# Sensor_Board.net
KiCad netlist of a schematic drawn in Altium Designer
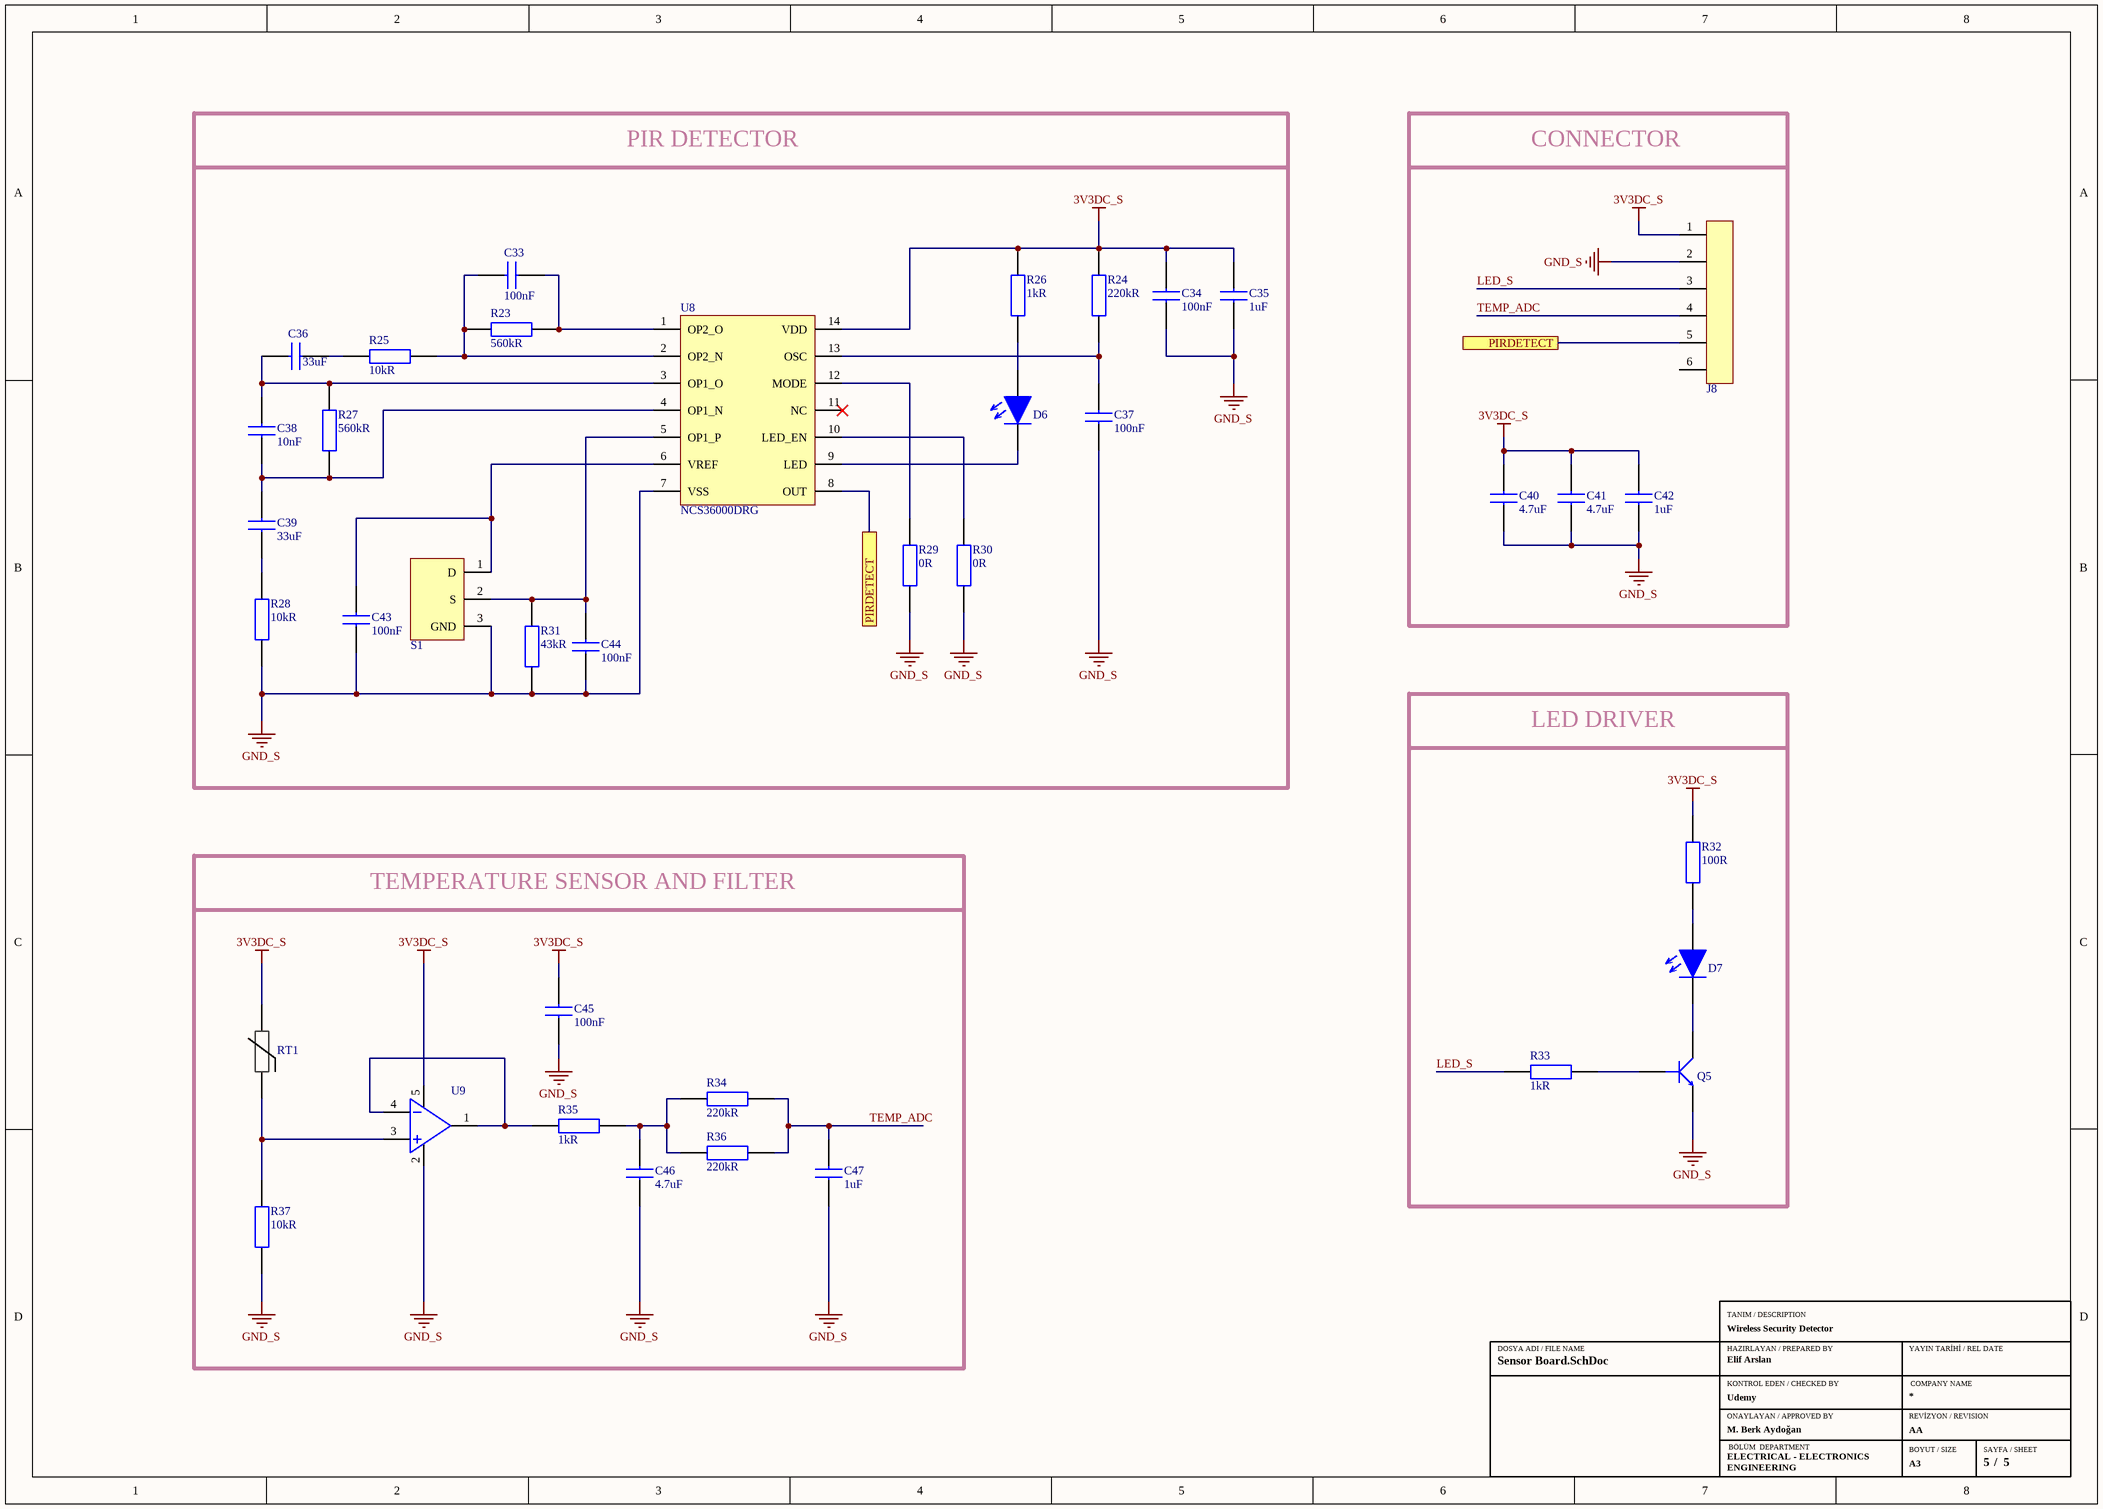
[diagram p0: Sensor Board.SchDoc]

(export (version "E")
  (design (tool "Eeschema 10.0.6"))
  (components
    (comp (ref "C33")
      (value "C0603C104K4RACTU")
      (footprint "CAP_0603")
      (description "CAP CER 100nF %10 0603 SMD")
      (fields
        (field (name "MANUFACTURER") "KEMET")
        (field (name "TOLERANCE") "10%")
        (field (name "CAPACITANCE") "100nF")
      )
      (libsource (lib "UDEMY_Library") (part "CAP CER 100nF 0603"))
    )
    (comp (ref "C34")
      (value "C0603C104K4RACTU")
      (footprint "CAP_0603")
      (description "CAP CER 100nF %10 0603 SMD")
      (fields
        (field (name "MANUFACTURER") "KEMET")
        (field (name "TOLERANCE") "10%")
        (field (name "CAPACITANCE") "100nF")
      )
      (libsource (lib "UDEMY_Library") (part "CAP CER 100nF 0603"))
    )
    (comp (ref "C35")
      (value "CL21B105KBFNNNE")
      (footprint "CAP_0805")
      (description "CAP CER 1UF %10 50V 0805")
      (fields
        (field (name "MANUFACTURER") "Samsung")
        (field (name "TOLERANCE") "10%")
        (field (name "CAPACITANCE") "1uF")
      )
      (libsource (lib "UDEMY_Library") (part "CAP CER 1uF 0805"))
    )
    (comp (ref "C36")
      (value "C3216X5R1E336M160AC")
      (footprint "RES_1206")
      (description "CAP CER 33uF %20 1206")
      (fields
        (field (name "MANUFACTURER") "TDK")
        (field (name "TOLERANCE") "20%")
        (field (name "CAPACITANCE") "33uF")
      )
      (libsource (lib "UDEMY_Library") (part "CAP CER 33uF 1206"))
    )
    (comp (ref "C37")
      (value "C0603C104K4RACTU")
      (footprint "CAP_0603")
      (description "CAP CER 100nF %10 0603 SMD")
      (fields
        (field (name "MANUFACTURER") "KEMET")
        (field (name "TOLERANCE") "10%")
        (field (name "CAPACITANCE") "100nF")
      )
      (libsource (lib "UDEMY_Library") (part "CAP CER 100nF 0603"))
    )
    (comp (ref "C38")
      (value "0603B103K160CT")
      (footprint "CAP_0603")
      (description "CAP CER 10nF %10 0603")
      (fields
        (field (name "MANUFACTURER") "Walsin Technologies")
        (field (name "TOLERANCE") "10%")
        (field (name "CAPACITANCE") "10nF")
      )
      (libsource (lib "UDEMY_Library") (part "CAP CER 10nF 0603"))
    )
    (comp (ref "C39")
      (value "C3216X5R1E336M160AC")
      (footprint "RES_1206")
      (description "CAP CER 33uF %20 1206")
      (fields
        (field (name "MANUFACTURER") "TDK")
        (field (name "TOLERANCE") "20%")
        (field (name "CAPACITANCE") "33uF")
      )
      (libsource (lib "UDEMY_Library") (part "CAP CER 33uF 1206"))
    )
    (comp (ref "C40")
      (value "CL21A475KAQNNNE")
      (footprint "CAP_0805")
      (description "CAP CER 4.7UF 25V X5R %10 0805")
      (fields
        (field (name "MANUFACTURER") "Samsung")
        (field (name "TOLERANCE") "10%")
        (field (name "CAPACITANCE") "4.7uF")
      )
      (libsource (lib "UDEMY_Library") (part "CAP CER  4.7uF 0805"))
    )
    (comp (ref "C41")
      (value "CL21A475KAQNNNE")
      (footprint "CAP_0805")
      (description "CAP CER 4.7UF 25V X5R %10 0805")
      (fields
        (field (name "MANUFACTURER") "Samsung")
        (field (name "TOLERANCE") "10%")
        (field (name "CAPACITANCE") "4.7uF")
      )
      (libsource (lib "UDEMY_Library") (part "CAP CER  4.7uF 0805"))
    )
    (comp (ref "C42")
      (value "CL21B105KBFNNNE")
      (footprint "CAP_0805")
      (description "CAP CER 1UF %10 50V 0805")
      (fields
        (field (name "MANUFACTURER") "Samsung")
        (field (name "TOLERANCE") "10%")
        (field (name "CAPACITANCE") "1uF")
      )
      (libsource (lib "UDEMY_Library") (part "CAP CER 1uF 0805"))
    )
    (comp (ref "C43")
      (value "C0603C104K4RACTU")
      (footprint "CAP_0603")
      (description "CAP CER 100nF %10 0603 SMD")
      (fields
        (field (name "MANUFACTURER") "KEMET")
        (field (name "TOLERANCE") "10%")
        (field (name "CAPACITANCE") "100nF")
      )
      (libsource (lib "UDEMY_Library") (part "CAP CER 100nF 0603"))
    )
    (comp (ref "C44")
      (value "C0603C104K4RACTU")
      (footprint "CAP_0603")
      (description "CAP CER 100nF %10 0603 SMD")
      (fields
        (field (name "MANUFACTURER") "KEMET")
        (field (name "TOLERANCE") "10%")
        (field (name "CAPACITANCE") "100nF")
      )
      (libsource (lib "UDEMY_Library") (part "CAP CER 100nF 0603"))
    )
    (comp (ref "C45")
      (value "C0603C104K4RACTU")
      (footprint "CAP_0603")
      (description "CAP CER 100nF %10 0603 SMD")
      (fields
        (field (name "MANUFACTURER") "KEMET")
        (field (name "TOLERANCE") "10%")
        (field (name "CAPACITANCE") "100nF")
      )
      (libsource (lib "UDEMY_Library") (part "CAP CER 100nF 0603"))
    )
    (comp (ref "C46")
      (value "CL21A475KAQNNNE")
      (footprint "CAP_0805")
      (description "CAP CER 4.7UF 25V X5R %10 0805")
      (fields
        (field (name "MANUFACTURER") "Samsung")
        (field (name "TOLERANCE") "10%")
        (field (name "CAPACITANCE") "4.7uF")
      )
      (libsource (lib "UDEMY_Library") (part "CAP CER  4.7uF 0805"))
    )
    (comp (ref "C47")
      (value "CL21B105KBFNNNE")
      (footprint "CAP_0805")
      (description "CAP CER 1UF %10 50V 0805")
      (fields
        (field (name "MANUFACTURER") "Samsung")
        (field (name "TOLERANCE") "10%")
        (field (name "CAPACITANCE") "1uF")
      )
      (libsource (lib "UDEMY_Library") (part "CAP CER 1uF 0805"))
    )
    (comp (ref "D6")
      (value "LTST-C171GKT")
      (footprint "LED_GREEN_0805")
      (description "Green 569nm LED Indication - Discrete 2.1V 0805 (2012 Metric)")
      (fields (field (name "MANUFACTURER") "Vishay Lite-On"))
      (libsource (lib "UDEMY_Library") (part "LED GREEN 0805"))
    )
    (comp (ref "D7")
      (value "LH R974-LP-1-0-20-R18")
      (footprint "LED_RED_0805")
      (description "LED Uni-Color Hyper Red 660nm 2-Pin Chip 0805(2012Metric) T/R")
      (fields
        (field (name "MANUFACTURER") "Osram Opto")
        (field (name "MANUFACTURER PART NUMBER") "LH R974-LP-1")
      )
      (libsource (lib "UDEMY_Library") (part "LED RED 0805"))
    )
    (comp (ref "J8")
      (value "64800611622")
      (footprint "64800611622")
      (description "1.5mm 6PIN Connector")
      (fields (field (name "MANUFACTURER") "Wurth Electronics"))
      (libsource (lib "UDEMY_Library") (part "64800611622_conn_6pin"))
    )
    (comp (ref "Q5")
      (value "MMBT3904-7-F")
      (footprint "SOT-23F")
      (description "Bipolar (BJT) Transistor NPN 40 V 200 mA 300MHz 300 mW Surface Mount SOT-23-3")
      (fields (field (name "MANUFACTURER") "Diodes Zetex"))
      (libsource (lib "UDEMY_Library") (part "MMBT3904-7-F"))
    )
    (comp (ref "R23")
      (value "RC0603JR-07560KL")
      (footprint "RES_0603")
      (description "RES SMD 560K OHM 5% 1/10W 0603")
      (fields
        (field (name "MANUFACTURER") "Yageo")
        (field (name "TOLERANCE") "5%")
        (field (name "RESISTANCE") "560kR")
      )
      (libsource (lib "UDEMY_Library") (part "RES 560K OHM 0603"))
    )
    (comp (ref "R24")
      (value "RC0603JR-07220KL")
      (footprint "RES_0603")
      (description "RES 220K OHM %5 0603 SMD")
      (fields
        (field (name "MANUFACTURER") "Yageo")
        (field (name "TOLERANCE") "5%")
        (field (name "RESISTANCE") "220kR")
      )
      (libsource (lib "UDEMY_Library") (part "RES 220K OHM 0603"))
    )
    (comp (ref "R25")
      (value "RC0603FR-0710KL")
      (footprint "RES_0603")
      (description "RES 10K %1 OHM 0603 SMD")
      (fields
        (field (name "MANUFACTURER") "Yageo")
        (field (name "TOLERANCE") "1%")
        (field (name "RESISTANCE") "10kR")
      )
      (libsource (lib "UDEMY_Library") (part "RES 10K OHM 0603"))
    )
    (comp (ref "R26")
      (value "RC0603FR-071KL")
      (footprint "RES_0603")
      (description "RES SMD 1K OHM %1 0603")
      (fields
        (field (name "MANUFACTURER") "Yageo")
        (field (name "TOLERANCE") "1%")
        (field (name "RESISTANCE") "1kR")
      )
      (libsource (lib "UDEMY_Library") (part "RES 1K OHM 0603"))
    )
    (comp (ref "R27")
      (value "RC0603JR-07560KL")
      (footprint "RES_0603")
      (description "RES SMD 560K OHM 5% 1/10W 0603")
      (fields
        (field (name "MANUFACTURER") "Yageo")
        (field (name "TOLERANCE") "5%")
        (field (name "RESISTANCE") "560kR")
      )
      (libsource (lib "UDEMY_Library") (part "RES 560K OHM 0603"))
    )
    (comp (ref "R28")
      (value "RC0603FR-0710KL")
      (footprint "RES_0603")
      (description "RES 10K %1 OHM 0603 SMD")
      (fields
        (field (name "MANUFACTURER") "Yageo")
        (field (name "TOLERANCE") "1%")
        (field (name "RESISTANCE") "10kR")
      )
      (libsource (lib "UDEMY_Library") (part "RES 10K OHM 0603"))
    )
    (comp (ref "R29")
      (value "RC0603JR-070RL")
      (footprint "RES_0603")
      (description "RES SMD 0 OHM JUMPER 1/10W 0603")
      (fields
        (field (name "MANUFACTURER") "Yageo")
        (field (name "TOLERANCE") "1%")
        (field (name "RESISTANCE") "0R")
      )
      (libsource (lib "UDEMY_Library") (part "RES 0 OHM 0603"))
    )
    (comp (ref "R30")
      (value "RC0603JR-070RL")
      (footprint "RES_0603")
      (description "RES SMD 0 OHM JUMPER 1/10W 0603")
      (fields
        (field (name "MANUFACTURER") "Yageo")
        (field (name "TOLERANCE") "1%")
        (field (name "RESISTANCE") "0R")
      )
      (libsource (lib "UDEMY_Library") (part "RES 0 OHM 0603"))
    )
    (comp (ref "R31")
      (value "RC0603JR-0743KL")
      (footprint "RES_0603")
      (description "RES 43K OHM %5 0603 SMD")
      (fields
        (field (name "MANUFACTURER") "Yageo")
        (field (name "TOLERANCE") "5%")
        (field (name "RESISTANCE") "43kR")
      )
      (libsource (lib "UDEMY_Library") (part "RES 43K OHM 0603"))
    )
    (comp (ref "R32")
      (value "RC0603JR-07100RL")
      (footprint "RES_0603")
      (description "RES 100 %5 OHM 0603 SMD")
      (fields
        (field (name "MANUFACTURER") "Yageo")
        (field (name "TOLERANCE") "5%")
        (field (name "RESISTANCE") "100R")
      )
      (libsource (lib "UDEMY_Library") (part "RES 100 OHM 0603"))
    )
    (comp (ref "R33")
      (value "RC0603FR-071KL")
      (footprint "RES_0603")
      (description "RES SMD 1K OHM %1 0603")
      (fields
        (field (name "MANUFACTURER") "Yageo")
        (field (name "TOLERANCE") "1%")
        (field (name "RESISTANCE") "1kR")
      )
      (libsource (lib "UDEMY_Library") (part "RES 1K OHM 0603"))
    )
    (comp (ref "R34")
      (value "RC0603JR-07220KL")
      (footprint "RES_0603")
      (description "RES 220K OHM %5 0603 SMD")
      (fields
        (field (name "MANUFACTURER") "Yageo")
        (field (name "TOLERANCE") "5%")
        (field (name "RESISTANCE") "220kR")
      )
      (libsource (lib "UDEMY_Library") (part "RES 220K OHM 0603"))
    )
    (comp (ref "R35")
      (value "RC0603FR-071KL")
      (footprint "RES_0603")
      (description "RES SMD 1K OHM %1 0603")
      (fields
        (field (name "MANUFACTURER") "Yageo")
        (field (name "TOLERANCE") "1%")
        (field (name "RESISTANCE") "1kR")
      )
      (libsource (lib "UDEMY_Library") (part "RES 1K OHM 0603"))
    )
    (comp (ref "R36")
      (value "RC0603JR-07220KL")
      (footprint "RES_0603")
      (description "RES 220K OHM %5 0603 SMD")
      (fields
        (field (name "MANUFACTURER") "Yageo")
        (field (name "TOLERANCE") "5%")
        (field (name "RESISTANCE") "220kR")
      )
      (libsource (lib "UDEMY_Library") (part "RES 220K OHM 0603"))
    )
    (comp (ref "R37")
      (value "RC0603FR-0710KL")
      (footprint "RES_0603")
      (description "RES 10K %1 OHM 0603 SMD")
      (fields
        (field (name "MANUFACTURER") "Yageo")
        (field (name "TOLERANCE") "1%")
        (field (name "RESISTANCE") "10kR")
      )
      (libsource (lib "UDEMY_Library") (part "RES 10K OHM 0603"))
    )
    (comp (ref "RT1")
      (value "TFPT1206L1002FM")
      (footprint "RES_1206")
      (description "Thermistor PTC 10K Ohm 1% 2-Pin 1206 Surface Mount Solder Pad T/R Automotive")
      (fields (field (name "MANUFACTURER") "Vishay Dale") (field (name "TOLERANCE") "1%"))
      (libsource (lib "UDEMY_Library") (part "TFPT1206L1002FM"))
    )
    (comp (ref "S1")
      (value "LHI 878/3902")
      (footprint "LHI 878")
      (description "Sensor Pyro Detector Dual Motion")
      (fields (field (name "MANUFACTURER") "Excelitas Technology"))
      (libsource (lib "UDEMY_Library") (part "LHI 878/3902"))
    )
    (comp (ref "U8")
      (value "NCS36000DRG")
      (footprint "SOIC14")
      (description "PIR Controller Low Noise Amplifiers and LDO Regulator 14-Pin SOIC N T/R")
      (fields (field (name "MANUFACTURER") "ON Semiconductor"))
      (libsource (lib "UDEMY_Library") (part "NCS 36000"))
    )
    (comp (ref "U9")
      (value "OPA314AIDBVR")
      (footprint "SOT23-5")
      (description "Op Amp OPA314 \r\nSOT23-5")
      (fields (field (name "MANUFACTURER") "Texas Instruments"))
      (libsource (lib "UDEMY_Library") (part "OPA314"))
    )
  )
  (nets
    (net (code "1") (name "/LED_S") (class "Default")
      (node (ref "J8") (pin "3") (pinfunction "3_3") (pintype "passive"))
      (node (ref "R33") (pin "1") (pinfunction "1_1") (pintype "passive"))
    )
    (net (code "2") (name "/PIRDETECT") (class "Default")
      (node (ref "J8") (pin "5") (pinfunction "5_5") (pintype "passive"))
      (node (ref "U8") (pin "8") (pinfunction "OUT_8") (pintype "passive"))
    )
    (net (code "3") (name "/TEMP_ADC") (class "Default")
      (node (ref "C47") (pin "2") (pinfunction "2_2") (pintype "passive"))
      (node (ref "J8") (pin "4") (pinfunction "4_4") (pintype "passive"))
      (node (ref "R34") (pin "2") (pinfunction "2_2") (pintype "passive"))
      (node (ref "R36") (pin "2") (pinfunction "2_2") (pintype "passive"))
    )
    (net (code "4") (name "3V3DC_S") (class "Default")
      (node (ref "C34") (pin "2") (pinfunction "2_2") (pintype "passive"))
      (node (ref "C35") (pin "2") (pinfunction "2_2") (pintype "passive"))
      (node (ref "C40") (pin "2") (pinfunction "2_2") (pintype "passive"))
      (node (ref "C41") (pin "2") (pinfunction "2_2") (pintype "passive"))
      (node (ref "C42") (pin "2") (pinfunction "2_2") (pintype "passive"))
      (node (ref "C45") (pin "2") (pinfunction "2_2") (pintype "passive"))
      (node (ref "J8") (pin "1") (pinfunction "1_1") (pintype "passive"))
      (node (ref "R24") (pin "2") (pinfunction "2_2") (pintype "passive"))
      (node (ref "R26") (pin "2") (pinfunction "2_2") (pintype "passive"))
      (node (ref "R32") (pin "2") (pinfunction "2_2") (pintype "passive"))
      (node (ref "RT1") (pin "2") (pinfunction "2_2") (pintype "passive"))
      (node (ref "U8") (pin "14") (pinfunction "VDD_14") (pintype "passive"))
      (node (ref "U9") (pin "5") (pinfunction "5_5") (pintype "passive"))
    )
    (net (code "5") (name "GND_S") (class "Default")
      (node (ref "C34") (pin "1") (pinfunction "1_1") (pintype "passive"))
      (node (ref "C35") (pin "1") (pinfunction "1_1") (pintype "passive"))
      (node (ref "C37") (pin "1") (pinfunction "1_1") (pintype "passive"))
      (node (ref "C40") (pin "1") (pinfunction "1_1") (pintype "passive"))
      (node (ref "C41") (pin "1") (pinfunction "1_1") (pintype "passive"))
      (node (ref "C42") (pin "1") (pinfunction "1_1") (pintype "passive"))
      (node (ref "C43") (pin "1") (pinfunction "1_1") (pintype "passive"))
      (node (ref "C44") (pin "1") (pinfunction "1_1") (pintype "passive"))
      (node (ref "C45") (pin "1") (pinfunction "1_1") (pintype "passive"))
      (node (ref "C46") (pin "1") (pinfunction "1_1") (pintype "passive"))
      (node (ref "C47") (pin "1") (pinfunction "1_1") (pintype "passive"))
      (node (ref "J8") (pin "2") (pinfunction "2_2") (pintype "passive"))
      (node (ref "Q5") (pin "2") (pinfunction "E_2") (pintype "passive"))
      (node (ref "R28") (pin "1") (pinfunction "1_1") (pintype "passive"))
      (node (ref "R29") (pin "1") (pinfunction "1_1") (pintype "passive"))
      (node (ref "R30") (pin "1") (pinfunction "1_1") (pintype "passive"))
      (node (ref "R31") (pin "1") (pinfunction "1_1") (pintype "passive"))
      (node (ref "R37") (pin "1") (pinfunction "1_1") (pintype "passive"))
      (node (ref "S1") (pin "3") (pinfunction "GND_3") (pintype "passive"))
      (node (ref "U8") (pin "7") (pinfunction "VSS_7") (pintype "passive"))
      (node (ref "U9") (pin "2") (pinfunction "2_2") (pintype "passive"))
    )
    (net (code "6") (name "Net-(C36-Pad2)") (class "Default")
      (node (ref "C36") (pin "2") (pinfunction "2_2") (pintype "passive"))
      (node (ref "R25") (pin "1") (pinfunction "1_1") (pintype "passive"))
    )
    (net (code "7") (name "Net-(C39-Pad1)") (class "Default")
      (node (ref "C39") (pin "1") (pinfunction "1_1") (pintype "passive"))
      (node (ref "R28") (pin "2") (pinfunction "2_2") (pintype "passive"))
    )
    (net (code "8") (name "Net-(C46-Pad2)") (class "Default")
      (node (ref "C46") (pin "2") (pinfunction "2_2") (pintype "passive"))
      (node (ref "R34") (pin "1") (pinfunction "1_1") (pintype "passive"))
      (node (ref "R35") (pin "2") (pinfunction "2_2") (pintype "passive"))
      (node (ref "R36") (pin "1") (pinfunction "1_1") (pintype "passive"))
    )
    (net (code "9") (name "Net-(D6-Pad2)") (class "Default")
      (node (ref "D6") (pin "2") (pinfunction "2_2") (pintype "passive"))
      (node (ref "R26") (pin "1") (pinfunction "1_1") (pintype "passive"))
    )
    (net (code "10") (name "Net-(D7-Pad2)") (class "Default")
      (node (ref "D7") (pin "2") (pinfunction "2_2") (pintype "passive"))
      (node (ref "R32") (pin "1") (pinfunction "1_1") (pintype "passive"))
    )
    (net (code "11") (name "Net-(Q5-B)") (class "Default")
      (node (ref "Q5") (pin "1") (pinfunction "B_1") (pintype "passive"))
      (node (ref "R33") (pin "2") (pinfunction "2_2") (pintype "passive"))
    )
    (net (code "12") (name "Net-(Q5-C)") (class "Default")
      (node (ref "D7") (pin "1") (pinfunction "1_1") (pintype "passive"))
      (node (ref "Q5") (pin "3") (pinfunction "C_3") (pintype "passive"))
    )
    (net (code "13") (name "Net-(R35-Pad1)") (class "Default")
      (node (ref "R35") (pin "1") (pinfunction "1_1") (pintype "passive"))
      (node (ref "U9") (pin "1") (pinfunction "1_1") (pintype "passive"))
      (node (ref "U9") (pin "4") (pinfunction "4_4") (pintype "passive"))
    )
    (net (code "14") (name "Net-(R37-Pad2)") (class "Default")
      (node (ref "R37") (pin "2") (pinfunction "2_2") (pintype "passive"))
      (node (ref "RT1") (pin "1") (pinfunction "1_1") (pintype "passive"))
      (node (ref "U9") (pin "3") (pinfunction "3_3") (pintype "passive"))
    )
    (net (code "15") (name "Net-(S1-D)") (class "Default")
      (node (ref "C43") (pin "2") (pinfunction "2_2") (pintype "passive"))
      (node (ref "S1") (pin "1") (pinfunction "D_1") (pintype "passive"))
      (node (ref "U8") (pin "6") (pinfunction "VREF_6") (pintype "passive"))
    )
    (net (code "16") (name "Net-(S1-S)") (class "Default")
      (node (ref "C44") (pin "2") (pinfunction "2_2") (pintype "passive"))
      (node (ref "R31") (pin "2") (pinfunction "2_2") (pintype "passive"))
      (node (ref "S1") (pin "2") (pinfunction "S_2") (pintype "passive"))
      (node (ref "U8") (pin "5") (pinfunction "OP1_P_5") (pintype "passive"))
    )
    (net (code "17") (name "Net-(U8-LED)") (class "Default")
      (node (ref "D6") (pin "1") (pinfunction "1_1") (pintype "passive"))
      (node (ref "U8") (pin "9") (pinfunction "LED_9") (pintype "passive"))
    )
    (net (code "18") (name "Net-(U8-LED_EN)") (class "Default")
      (node (ref "R30") (pin "2") (pinfunction "2_2") (pintype "passive"))
      (node (ref "U8") (pin "10") (pinfunction "LED_EN_10") (pintype "passive"))
    )
    (net (code "19") (name "Net-(U8-MODE)") (class "Default")
      (node (ref "R29") (pin "2") (pinfunction "2_2") (pintype "passive"))
      (node (ref "U8") (pin "12") (pinfunction "MODE_12") (pintype "passive"))
    )
    (net (code "20") (name "Net-(U8-OP1_N)") (class "Default")
      (node (ref "C38") (pin "1") (pinfunction "1_1") (pintype "passive"))
      (node (ref "C39") (pin "2") (pinfunction "2_2") (pintype "passive"))
      (node (ref "R27") (pin "1") (pinfunction "1_1") (pintype "passive"))
      (node (ref "U8") (pin "4") (pinfunction "OP1_N_4") (pintype "passive"))
    )
    (net (code "21") (name "Net-(U8-OP1_O)") (class "Default")
      (node (ref "C36") (pin "1") (pinfunction "1_1") (pintype "passive"))
      (node (ref "C38") (pin "2") (pinfunction "2_2") (pintype "passive"))
      (node (ref "R27") (pin "2") (pinfunction "2_2") (pintype "passive"))
      (node (ref "U8") (pin "3") (pinfunction "OP1_O_3") (pintype "passive"))
    )
    (net (code "22") (name "Net-(U8-OP2_N)") (class "Default")
      (node (ref "C33") (pin "1") (pinfunction "1_1") (pintype "passive"))
      (node (ref "R23") (pin "1") (pinfunction "1_1") (pintype "passive"))
      (node (ref "R25") (pin "2") (pinfunction "2_2") (pintype "passive"))
      (node (ref "U8") (pin "2") (pinfunction "OP2_N_2") (pintype "passive"))
    )
    (net (code "23") (name "Net-(U8-OP2_O)") (class "Default")
      (node (ref "C33") (pin "2") (pinfunction "2_2") (pintype "passive"))
      (node (ref "R23") (pin "2") (pinfunction "2_2") (pintype "passive"))
      (node (ref "U8") (pin "1") (pinfunction "OP2_O_1") (pintype "passive"))
    )
    (net (code "24") (name "Net-(U8-OSC)") (class "Default")
      (node (ref "C37") (pin "2") (pinfunction "2_2") (pintype "passive"))
      (node (ref "R24") (pin "1") (pinfunction "1_1") (pintype "passive"))
      (node (ref "U8") (pin "13") (pinfunction "OSC_13") (pintype "passive"))
    )
    (net (code "25") (name "unconnected-(J8-Pad6)") (class "Default")
      (node (ref "J8") (pin "6") (pinfunction "6_6") (pintype "passive"))
    )
    (net (code "26") (name "unconnected-(U8-NC-Pad11)") (class "Default")
      (node (ref "U8") (pin "11") (pinfunction "NC_11") (pintype "passive+no_connect"))
    )
  )
)
